# board.net
KiCad netlist of a schematic drawn in EAGLE
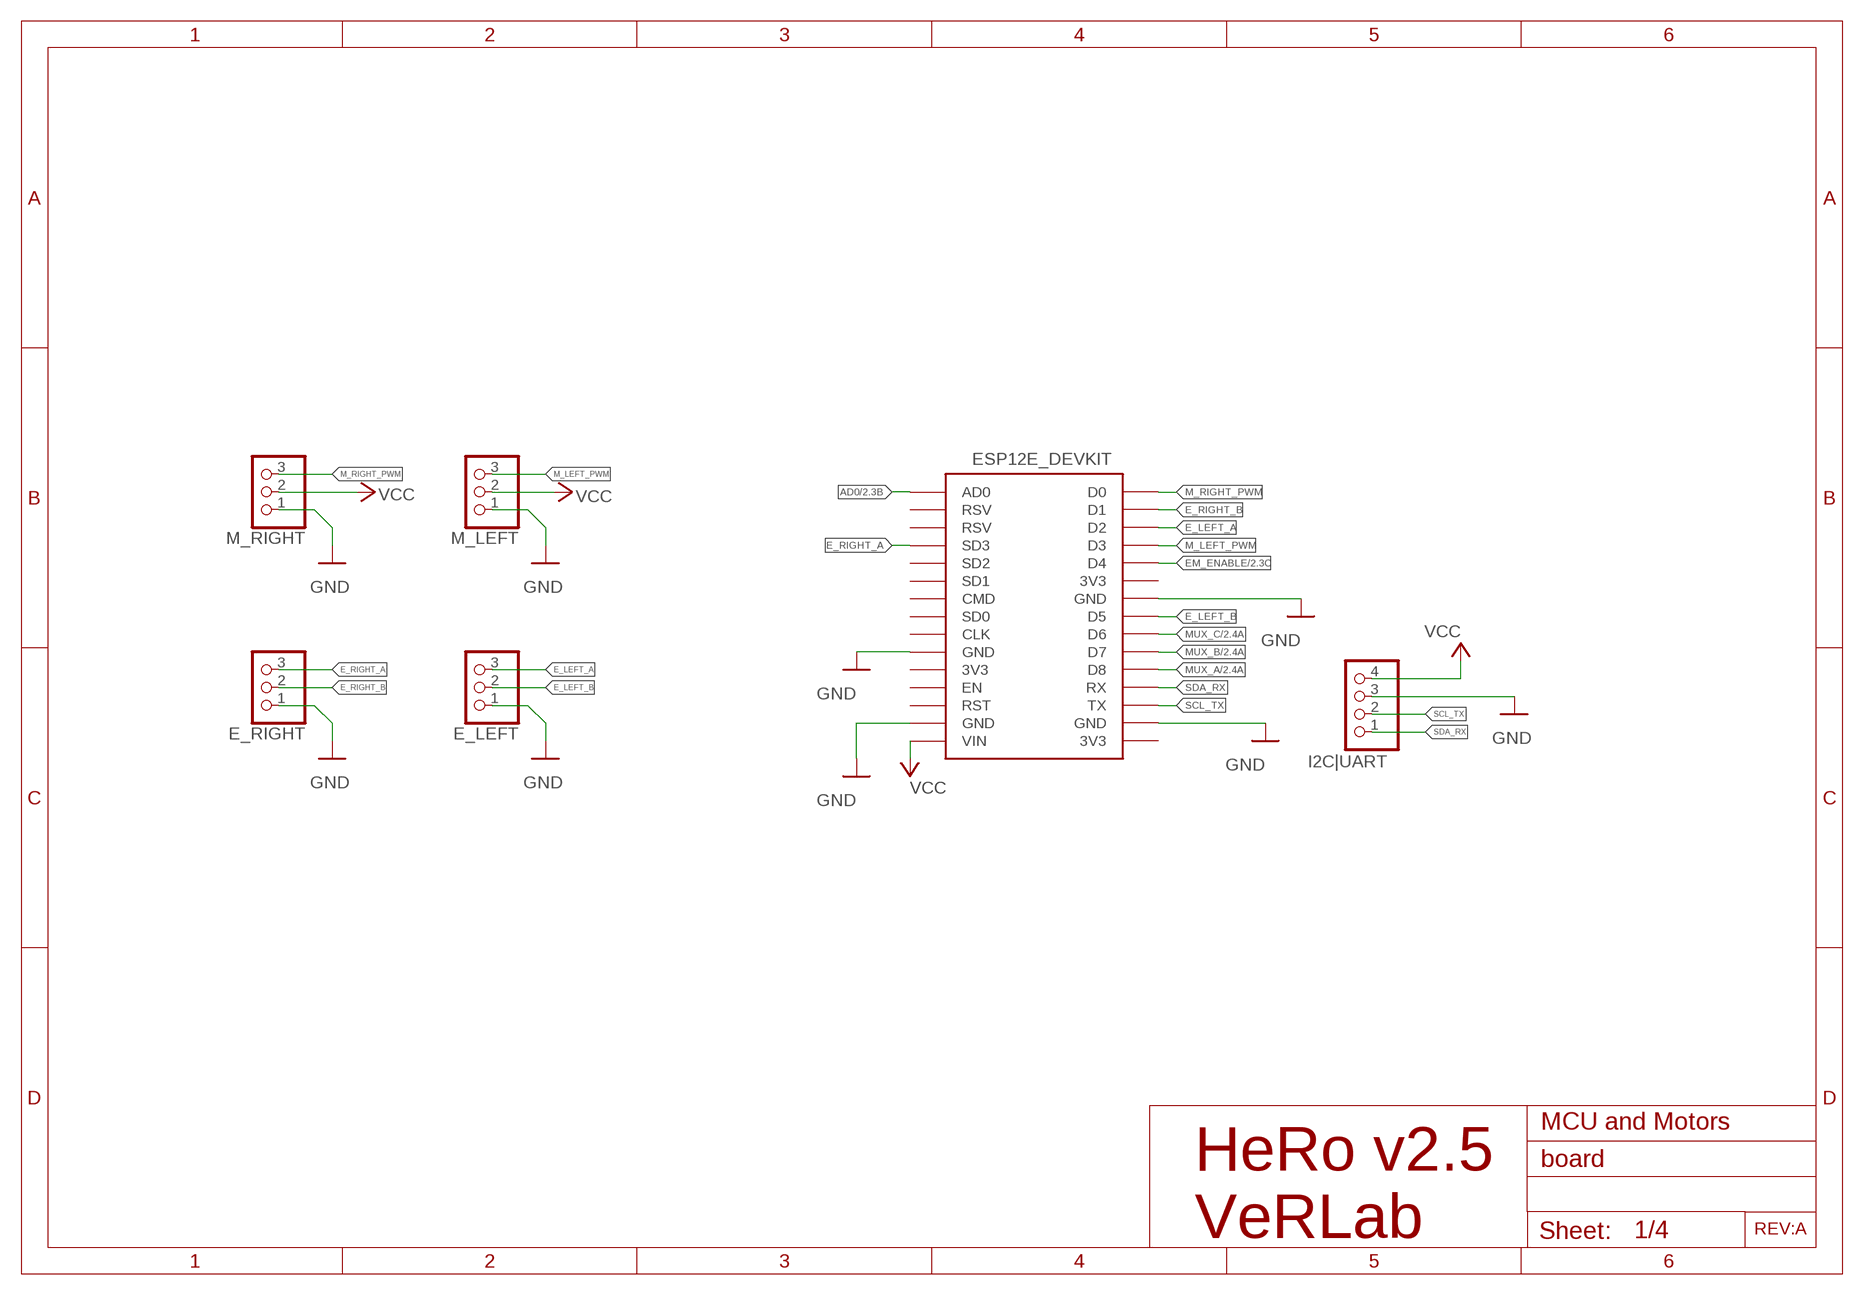
[diagram p0: schematic, sheet 1]
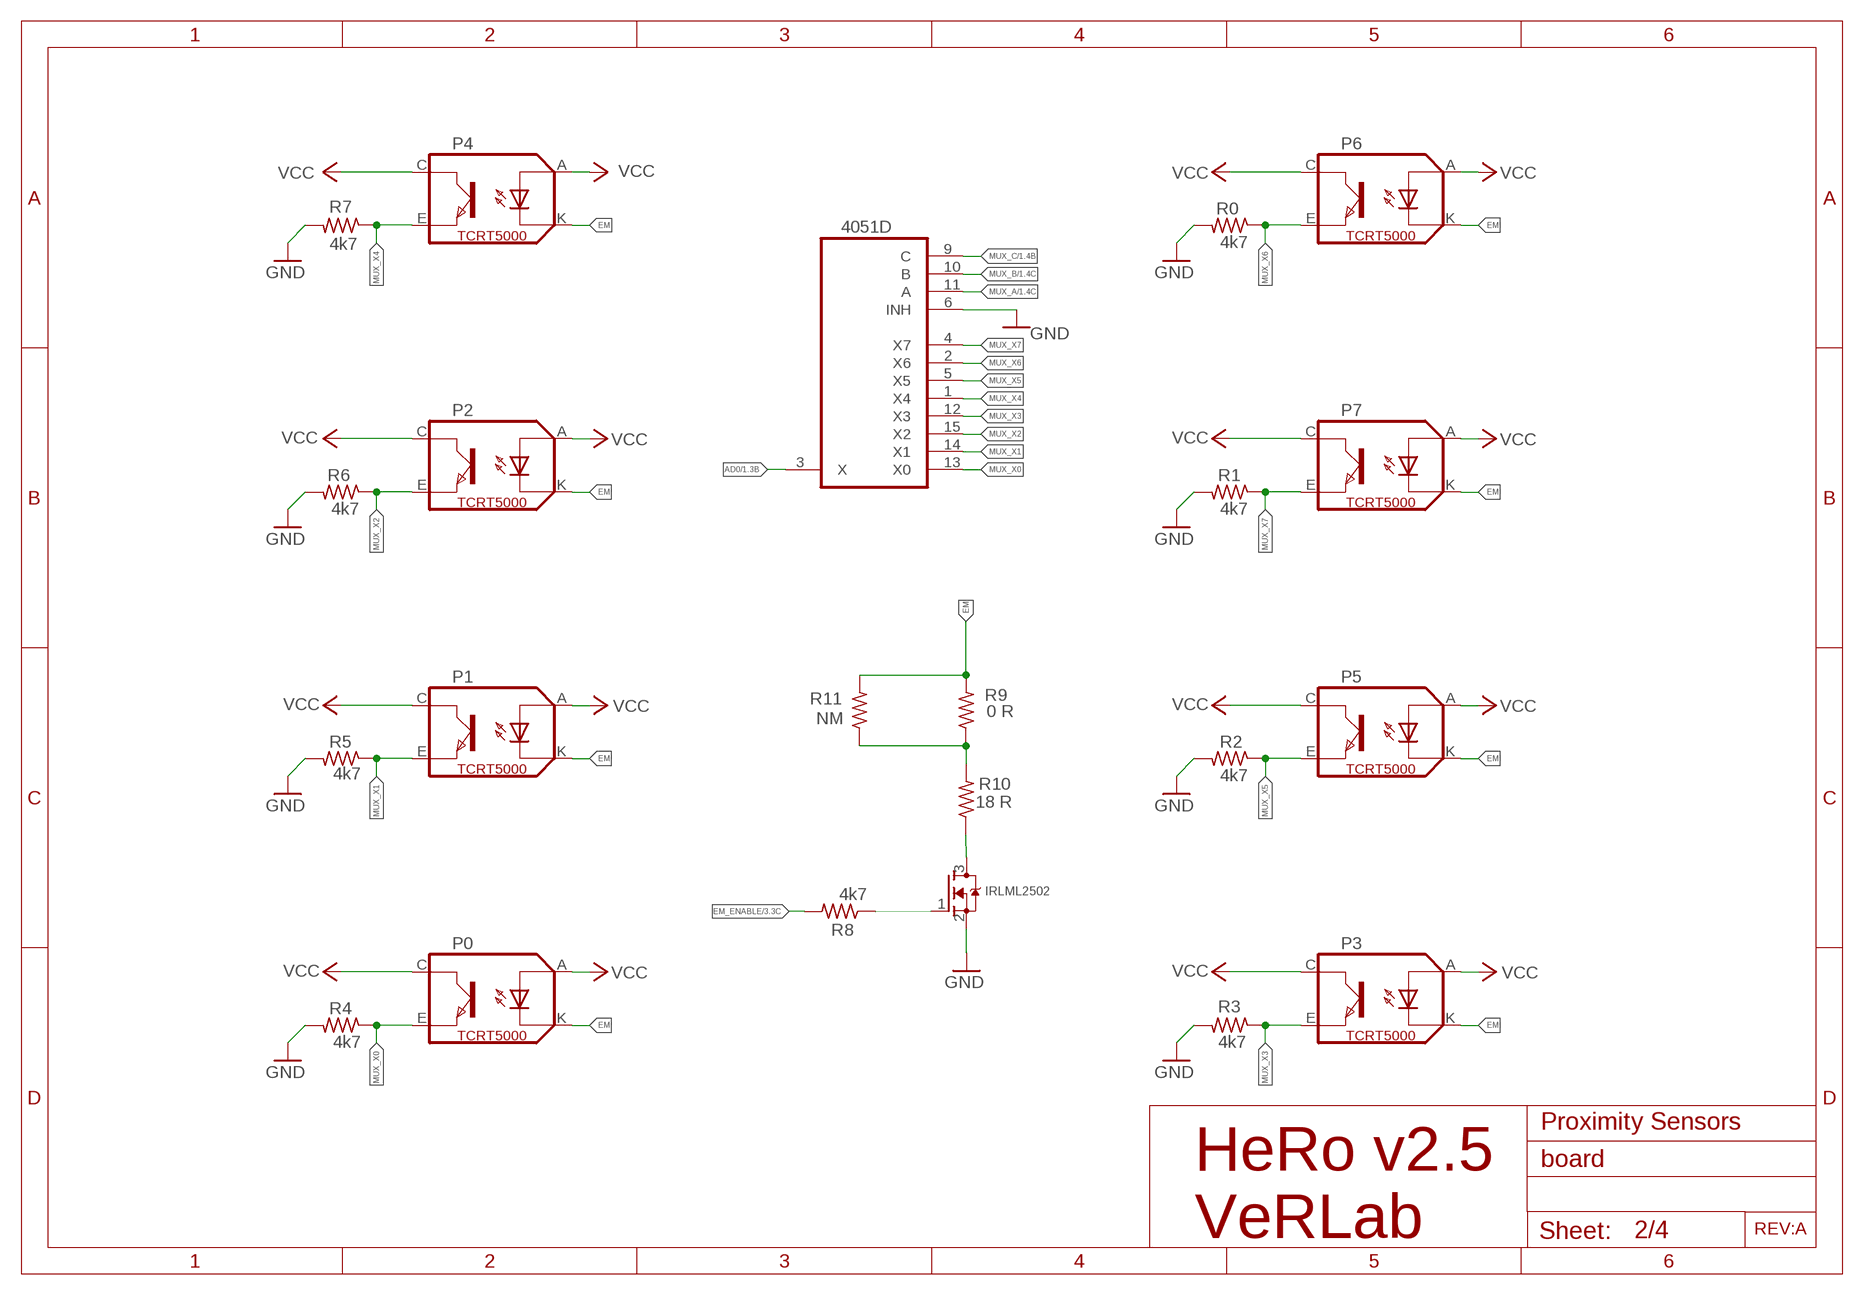
[diagram p1: schematic, sheet 2]
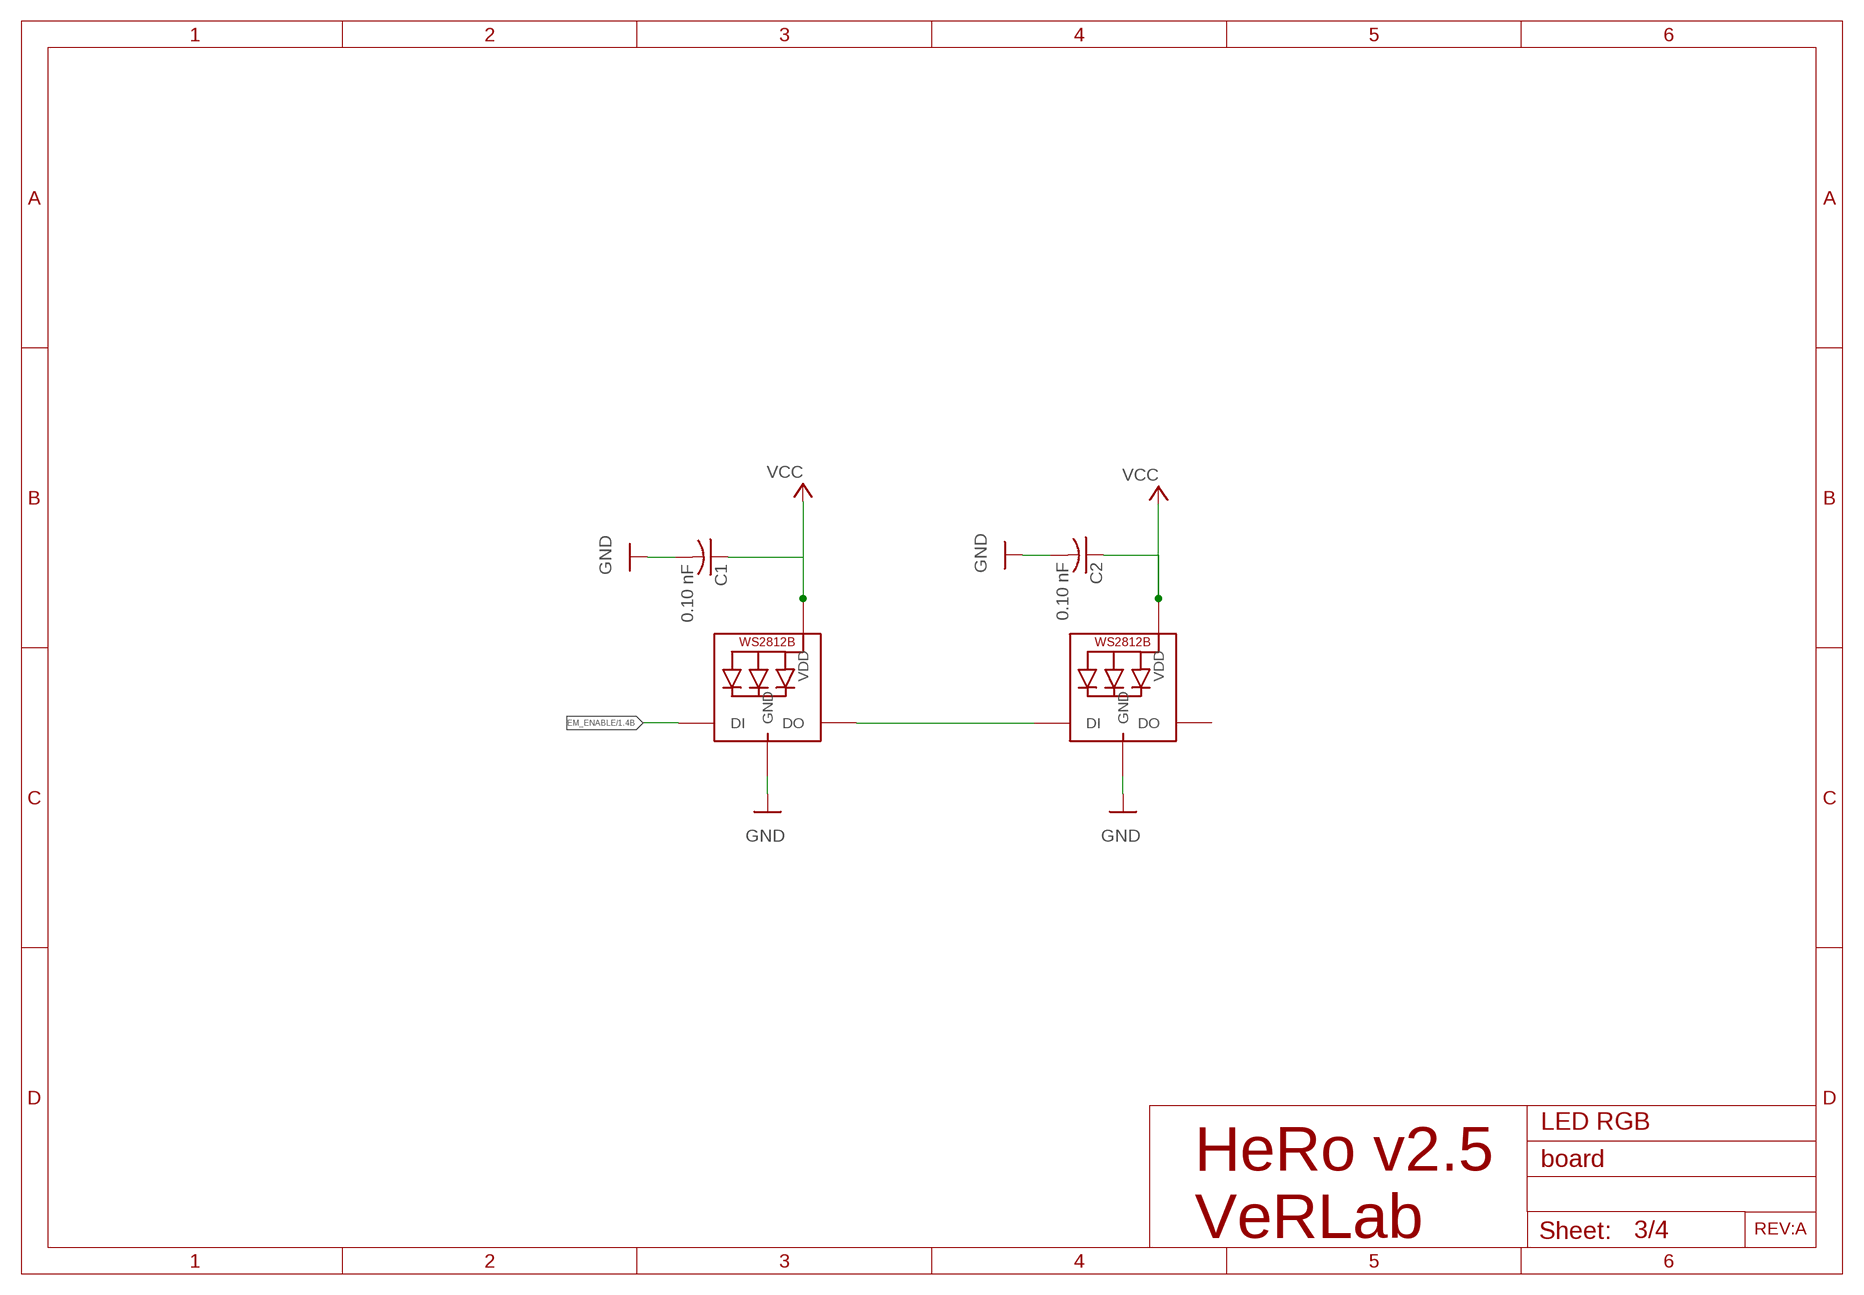
[diagram p2: schematic, sheet 3]
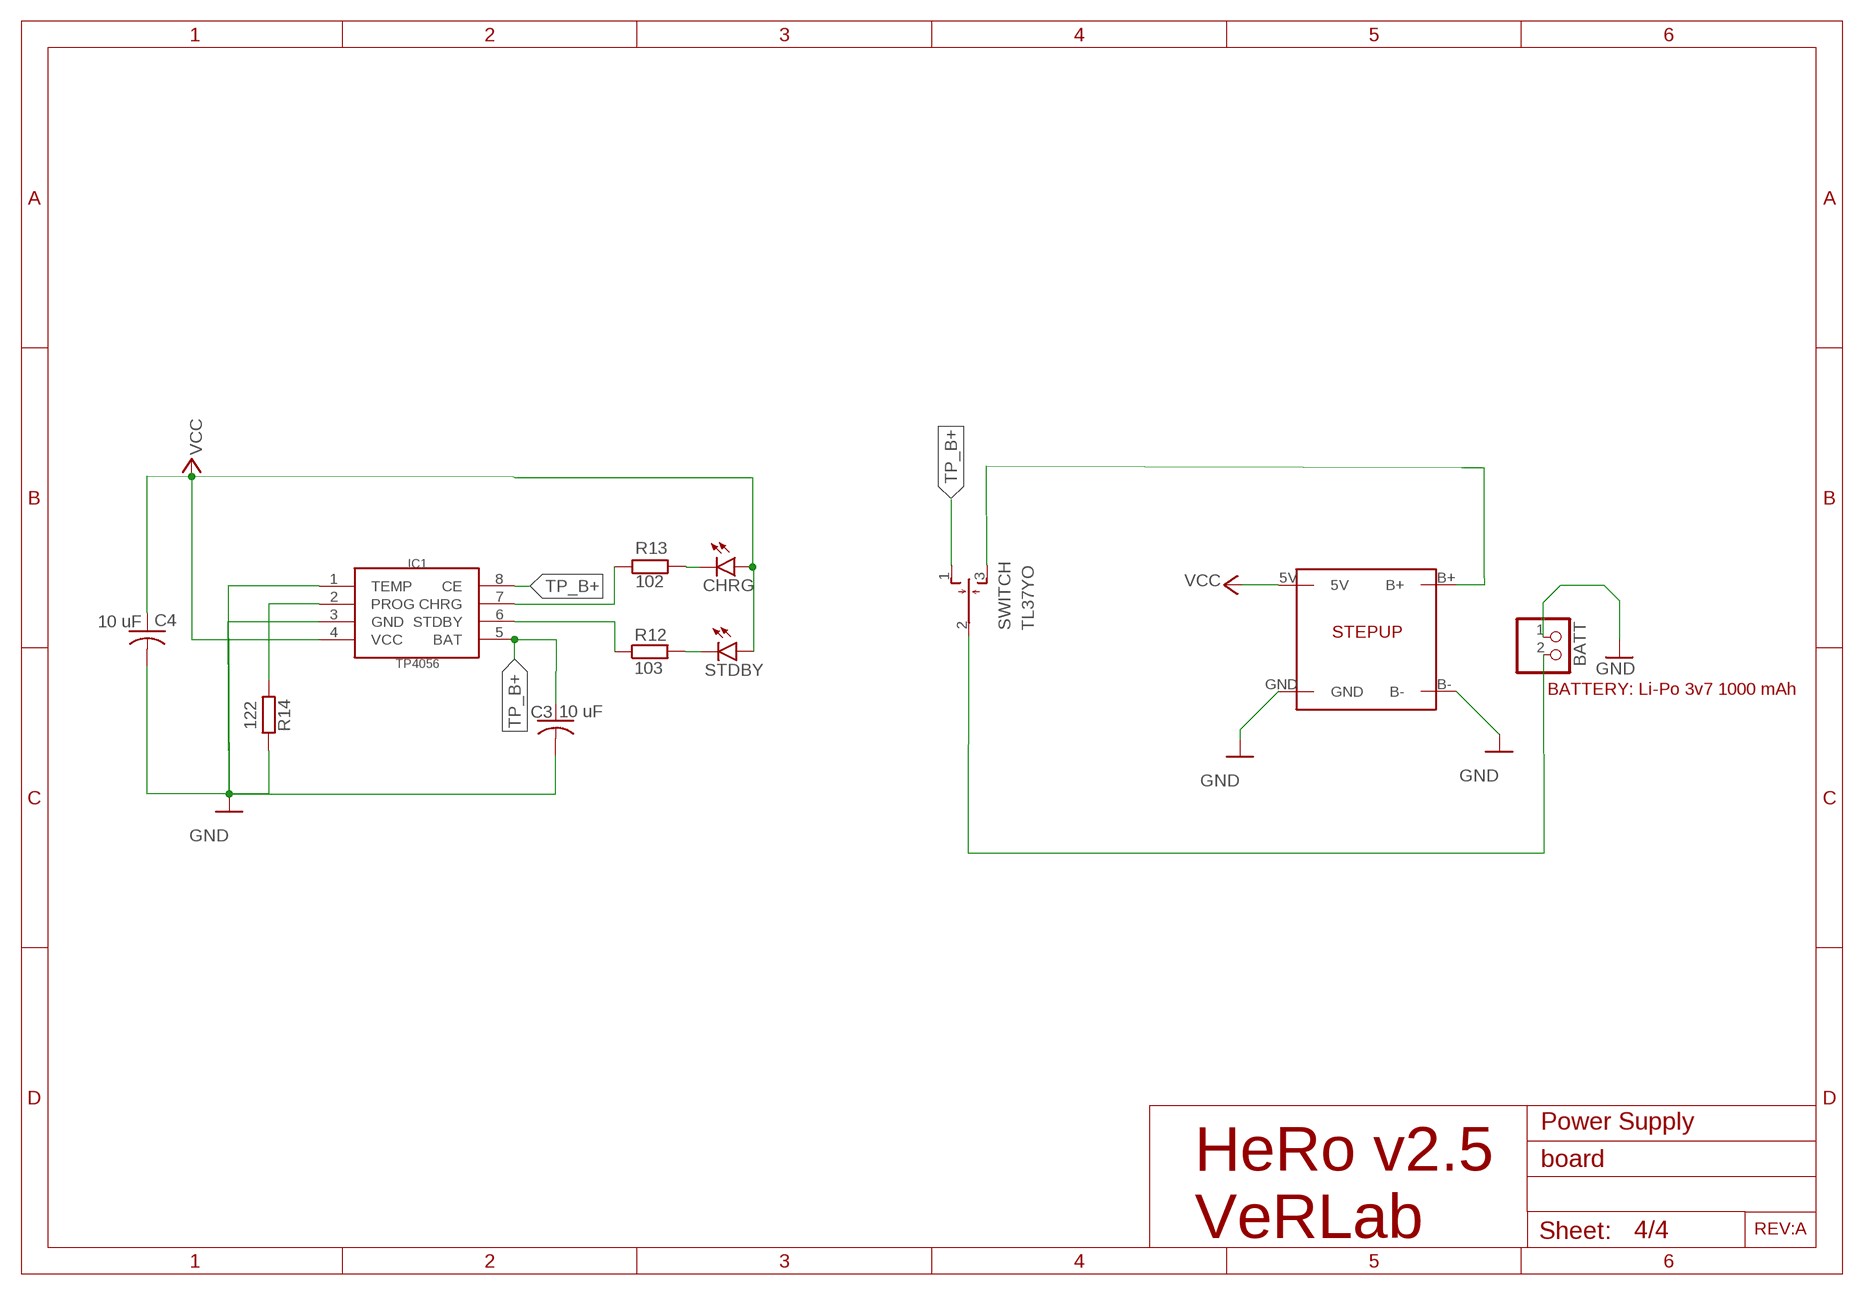
[diagram p3: schematic, sheet 4]

(export (version "E")
  (design (tool "Eeschema 10.0.6"))
  (components
    (comp (ref "BATT")
      (value "PINHD-1X2")
      (footprint "eagle-import:1X02")
      (libsource (lib "eagle-import") (part "PINHD-1X2"))
    )
    (comp (ref "C3")
      (value "10 uF")
      (footprint "eagle-import:C0603")
      (libsource (lib "eagle-import") (part "resistor_348_C-USC0603"))
    )
    (comp (ref "C4")
      (value "10 uF")
      (footprint "eagle-import:C0603")
      (libsource (lib "eagle-import") (part "resistor_348_C-USC0603"))
    )
    (comp (ref "CHRG")
      (value "LEDSML0805")
      (footprint "eagle-import:SML0805")
      (libsource (lib "eagle-import") (part "LEDSML0805"))
    )
    (comp (ref "IC1")
      (value "TP4056")
      (footprint "eagle-import:SOP-8")
      (fields (field (name "SPICEPREFIX") "X"))
      (libsource (lib "eagle-import") (part "TP4056"))
    )
    (comp (ref "OS1")
      (value "STEPUP")
      (footprint "eagle-import:STEPUP")
      (libsource (lib "eagle-import") (part "STEPUP"))
    )
    (comp (ref "R12")
      (value "103")
      (footprint "eagle-import:R0805")
      (libsource (lib "eagle-import") (part "R-EU_R0805"))
    )
    (comp (ref "R13")
      (value "102")
      (footprint "eagle-import:R0805")
      (libsource (lib "eagle-import") (part "R-EU_R0805"))
    )
    (comp (ref "R14")
      (value "122")
      (footprint "eagle-import:R0603")
      (libsource (lib "eagle-import") (part "R-EU_R0603"))
    )
    (comp (ref "STDBY")
      (value "LEDSML0805")
      (footprint "eagle-import:SML0805")
      (libsource (lib "eagle-import") (part "LEDSML0805"))
    )
    (comp (ref "SWITCH")
      (value "TL37YO")
      (footprint "eagle-import:TL3XYO")
      (libsource (lib "eagle-import") (part "TL37YO"))
    )
    (comp (ref "E_LEFT")
      (value "PINHD-1X3")
      (footprint "eagle-import:1X03")
      (libsource (lib "eagle-import") (part "PINHD-1X3"))
    )
    (comp (ref "E_RIGHT")
      (value "PINHD-1X3")
      (footprint "eagle-import:1X03")
      (libsource (lib "eagle-import") (part "PINHD-1X3"))
    )
    (comp (ref "I2C|UART")
      (value "PINHD-1X4")
      (footprint "eagle-import:1X04")
      (libsource (lib "eagle-import") (part "PINHD-1X4"))
    )
    (comp (ref "M_LEFT")
      (value "PINHD-1X3")
      (footprint "eagle-import:1X03")
      (libsource (lib "eagle-import") (part "PINHD-1X3"))
    )
    (comp (ref "M_RIGHT")
      (value "PINHD-1X3")
      (footprint "eagle-import:1X03")
      (libsource (lib "eagle-import") (part "PINHD-1X3"))
    )
    (comp (ref "U$1")
      (value "ESP12E_DEVKIT")
      (footprint "eagle-import:ESP12E_DEVKIT")
      (libsource (lib "eagle-import") (part "ESP12E_DEVKIT"))
    )
    (comp (ref "IC2")
      (value "4051D")
      (footprint "eagle-import:SO16")
      (libsource (lib "eagle-import") (part "4051D"))
    )
    (comp (ref "IRLML2502")
      (value "MOSFET-NREFLOW")
      (footprint "eagle-import:SOT23")
      (libsource (lib "eagle-import") (part "MOSFET-NREFLOW"))
    )
    (comp (ref "P0")
      (value "TCRT5000")
      (footprint "eagle-import:TCRT5000")
      (libsource (lib "eagle-import") (part "TCRT5000"))
    )
    (comp (ref "P1")
      (value "TCRT5000")
      (footprint "eagle-import:TCRT5000")
      (libsource (lib "eagle-import") (part "TCRT5000"))
    )
    (comp (ref "P2")
      (value "TCRT5000")
      (footprint "eagle-import:TCRT5000")
      (libsource (lib "eagle-import") (part "TCRT5000"))
    )
    (comp (ref "P3")
      (value "TCRT5000")
      (footprint "eagle-import:TCRT5000")
      (libsource (lib "eagle-import") (part "TCRT5000"))
    )
    (comp (ref "P4")
      (value "TCRT5000")
      (footprint "eagle-import:TCRT5000")
      (libsource (lib "eagle-import") (part "TCRT5000"))
    )
    (comp (ref "P5")
      (value "TCRT5000")
      (footprint "eagle-import:TCRT5000")
      (libsource (lib "eagle-import") (part "TCRT5000"))
    )
    (comp (ref "P6")
      (value "TCRT5000")
      (footprint "eagle-import:TCRT5000")
      (libsource (lib "eagle-import") (part "TCRT5000"))
    )
    (comp (ref "P7")
      (value "TCRT5000")
      (footprint "eagle-import:TCRT5000")
      (libsource (lib "eagle-import") (part "TCRT5000"))
    )
    (comp (ref "R0")
      (value "4k7")
      (footprint "eagle-import:M0805")
      (libsource (lib "eagle-import") (part "R-US_M0805"))
    )
    (comp (ref "R1")
      (value "4k7")
      (footprint "eagle-import:M0805")
      (libsource (lib "eagle-import") (part "R-US_M0805"))
    )
    (comp (ref "R2")
      (value "4k7")
      (footprint "eagle-import:M0805")
      (libsource (lib "eagle-import") (part "R-US_M0805"))
    )
    (comp (ref "R3")
      (value "4k7")
      (footprint "eagle-import:M0805")
      (libsource (lib "eagle-import") (part "R-US_M0805"))
    )
    (comp (ref "R4")
      (value "4k7")
      (footprint "eagle-import:M0805")
      (libsource (lib "eagle-import") (part "R-US_M0805"))
    )
    (comp (ref "R5")
      (value "4k7")
      (footprint "eagle-import:M0805")
      (libsource (lib "eagle-import") (part "R-US_M0805"))
    )
    (comp (ref "R6")
      (value "4k7")
      (footprint "eagle-import:M0805")
      (libsource (lib "eagle-import") (part "R-US_M0805"))
    )
    (comp (ref "R7")
      (value "4k7")
      (footprint "eagle-import:M0805")
      (libsource (lib "eagle-import") (part "R-US_M0805"))
    )
    (comp (ref "R8")
      (value "4k7")
      (footprint "eagle-import:R0805")
      (fields (field (name "SPICEPREFIX") "R"))
      (libsource (lib "eagle-import") (part "resistor_348_R-US_R0805"))
    )
    (comp (ref "R9")
      (value "0 R")
      (footprint "eagle-import:R0805")
      (fields (field (name "SPICEPREFIX") "R"))
      (libsource (lib "eagle-import") (part "resistor_348_R-US_R0805"))
    )
    (comp (ref "R10")
      (value "18 R")
      (footprint "eagle-import:R0805")
      (fields (field (name "SPICEPREFIX") "R"))
      (libsource (lib "eagle-import") (part "resistor_348_R-US_R0805"))
    )
    (comp (ref "R11")
      (value "NM")
      (footprint "eagle-import:R0805")
      (fields (field (name "SPICEPREFIX") "R"))
      (libsource (lib "eagle-import") (part "resistor_348_R-US_R0805"))
    )
    (comp (ref "C1")
      (value "0.10 nF")
      (footprint "eagle-import:C0603")
      (libsource (lib "eagle-import") (part "C-USC0603"))
    )
    (comp (ref "C2")
      (value "0.10 nF")
      (footprint "eagle-import:C0603")
      (libsource (lib "eagle-import") (part "C-USC0603"))
    )
    (comp (ref "LED0")
      (value "WS2812B5050")
      (footprint "eagle-import:WS2812B")
      (libsource (lib "eagle-import") (part "WS2812B5050"))
    )
    (comp (ref "LED1")
      (value "WS2812B5050")
      (footprint "eagle-import:WS2812B")
      (libsource (lib "eagle-import") (part "WS2812B5050"))
    )
  )
  (nets
    (net (code "1") (name "AD0") (class "Default")
      (node (ref "IC2") (pin "3") (pinfunction "X_3") (pintype "bidirectional"))
      (node (ref "U$1") (pin "AD0") (pinfunction "AD0_AD0") (pintype "bidirectional"))
    )
    (net (code "2") (name "EM") (class "Default")
      (node (ref "P0") (pin "K") (pinfunction "CATHODE_K") (pintype "passive"))
      (node (ref "P1") (pin "K") (pinfunction "CATHODE_K") (pintype "passive"))
      (node (ref "P2") (pin "K") (pinfunction "CATHODE_K") (pintype "passive"))
      (node (ref "P3") (pin "K") (pinfunction "CATHODE_K") (pintype "passive"))
      (node (ref "P4") (pin "K") (pinfunction "CATHODE_K") (pintype "passive"))
      (node (ref "P5") (pin "K") (pinfunction "CATHODE_K") (pintype "passive"))
      (node (ref "P6") (pin "K") (pinfunction "CATHODE_K") (pintype "passive"))
      (node (ref "P7") (pin "K") (pinfunction "CATHODE_K") (pintype "passive"))
      (node (ref "R11") (pin "2") (pinfunction "2_2") (pintype "passive"))
      (node (ref "R9") (pin "2") (pinfunction "2_2") (pintype "passive"))
    )
    (net (code "3") (name "EM_ENABLE") (class "Default")
      (node (ref "LED0") (pin "4-DIN") (pinfunction "DI_4-DIN") (pintype "input"))
      (node (ref "R8") (pin "2") (pinfunction "2_2") (pintype "passive"))
      (node (ref "U$1") (pin "D4") (pinfunction "D4_D4") (pintype "bidirectional"))
    )
    (net (code "4") (name "E_LEFT_A") (class "Default")
      (node (ref "E_LEFT") (pin "3") (pinfunction "3_3") (pintype "passive"))
      (node (ref "U$1") (pin "D2") (pinfunction "D2_D2") (pintype "bidirectional"))
    )
    (net (code "5") (name "E_LEFT_B") (class "Default")
      (node (ref "E_LEFT") (pin "2") (pinfunction "2_2") (pintype "passive"))
      (node (ref "U$1") (pin "D5") (pinfunction "D5_D5") (pintype "bidirectional"))
    )
    (net (code "6") (name "E_RIGHT_A") (class "Default")
      (node (ref "E_RIGHT") (pin "3") (pinfunction "3_3") (pintype "passive"))
      (node (ref "U$1") (pin "SD3") (pinfunction "SD3_SD3") (pintype "bidirectional"))
    )
    (net (code "7") (name "E_RIGHT_B") (class "Default")
      (node (ref "E_RIGHT") (pin "2") (pinfunction "2_2") (pintype "passive"))
      (node (ref "U$1") (pin "D1") (pinfunction "D1_D1") (pintype "bidirectional"))
    )
    (net (code "8") (name "GND") (class "Default")
      (node (ref "BATT") (pin "1") (pinfunction "1_1") (pintype "passive"))
      (node (ref "C1") (pin "2") (pinfunction "2_2") (pintype "passive"))
      (node (ref "C2") (pin "2") (pinfunction "2_2") (pintype "passive"))
      (node (ref "C3") (pin "2") (pinfunction "2_2") (pintype "passive"))
      (node (ref "C4") (pin "2") (pinfunction "2_2") (pintype "passive"))
      (node (ref "E_LEFT") (pin "1") (pinfunction "1_1") (pintype "passive"))
      (node (ref "E_RIGHT") (pin "1") (pinfunction "1_1") (pintype "passive"))
      (node (ref "I2C|UART") (pin "3") (pinfunction "3_3") (pintype "passive"))
      (node (ref "IC1") (pin "1") (pinfunction "TEMP_1") (pintype "bidirectional"))
      (node (ref "IC1") (pin "3") (pinfunction "GND_3") (pintype "bidirectional"))
      (node (ref "IC2") (pin "6") (pinfunction "INH_6") (pintype "input"))
      (node (ref "IRLML2502") (pin "2") (pinfunction "S_2") (pintype "bidirectional"))
      (node (ref "LED0") (pin "3-GND") (pinfunction "GND_3-GND") (pintype "power_in"))
      (node (ref "LED1") (pin "3-GND") (pinfunction "GND_3-GND") (pintype "power_in"))
      (node (ref "M_LEFT") (pin "1") (pinfunction "1_1") (pintype "passive"))
      (node (ref "M_RIGHT") (pin "1") (pinfunction "1_1") (pintype "passive"))
      (node (ref "OS1") (pin "B-") (pinfunction "B-_B-") (pintype "input"))
      (node (ref "OS1") (pin "GND") (pinfunction "GND_GND") (pintype "output"))
      (node (ref "R0") (pin "2") (pinfunction "2_2") (pintype "passive"))
      (node (ref "R1") (pin "2") (pinfunction "2_2") (pintype "passive"))
      (node (ref "R14") (pin "1") (pinfunction "1_1") (pintype "passive"))
      (node (ref "R2") (pin "2") (pinfunction "2_2") (pintype "passive"))
      (node (ref "R3") (pin "2") (pinfunction "2_2") (pintype "passive"))
      (node (ref "R4") (pin "2") (pinfunction "2_2") (pintype "passive"))
      (node (ref "R5") (pin "2") (pinfunction "2_2") (pintype "passive"))
      (node (ref "R6") (pin "2") (pinfunction "2_2") (pintype "passive"))
      (node (ref "R7") (pin "2") (pinfunction "2_2") (pintype "passive"))
      (node (ref "U$1") (pin "GND@0") (pinfunction "GND_GND@0") (pintype "bidirectional"))
      (node (ref "U$1") (pin "GND@1") (pinfunction "GND_GND@1") (pintype "bidirectional"))
      (node (ref "U$1") (pin "GND@2") (pinfunction "GND_GND@2") (pintype "bidirectional"))
      (node (ref "U$1") (pin "GND@3") (pinfunction "GND_GND@3") (pintype "bidirectional"))
    )
    (net (code "9") (name "MUX_A") (class "Default")
      (node (ref "IC2") (pin "11") (pinfunction "A_11") (pintype "input"))
      (node (ref "U$1") (pin "D8") (pinfunction "D8_D8") (pintype "bidirectional"))
    )
    (net (code "10") (name "MUX_B") (class "Default")
      (node (ref "IC2") (pin "10") (pinfunction "B_10") (pintype "input"))
      (node (ref "U$1") (pin "D7") (pinfunction "D7_D7") (pintype "bidirectional"))
    )
    (net (code "11") (name "MUX_C") (class "Default")
      (node (ref "IC2") (pin "9") (pinfunction "C_9") (pintype "input"))
      (node (ref "U$1") (pin "D6") (pinfunction "D6_D6") (pintype "bidirectional"))
    )
    (net (code "12") (name "MUX_X0") (class "Default")
      (node (ref "IC2") (pin "13") (pinfunction "X0_13") (pintype "bidirectional"))
      (node (ref "P0") (pin "E") (pinfunction "EMITTER_E") (pintype "passive"))
      (node (ref "R4") (pin "1") (pinfunction "1_1") (pintype "passive"))
    )
    (net (code "13") (name "MUX_X1") (class "Default")
      (node (ref "IC2") (pin "14") (pinfunction "X1_14") (pintype "bidirectional"))
      (node (ref "P1") (pin "E") (pinfunction "EMITTER_E") (pintype "passive"))
      (node (ref "R5") (pin "1") (pinfunction "1_1") (pintype "passive"))
    )
    (net (code "14") (name "MUX_X2") (class "Default")
      (node (ref "IC2") (pin "15") (pinfunction "X2_15") (pintype "bidirectional"))
      (node (ref "P2") (pin "E") (pinfunction "EMITTER_E") (pintype "passive"))
      (node (ref "R6") (pin "1") (pinfunction "1_1") (pintype "passive"))
    )
    (net (code "15") (name "MUX_X3") (class "Default")
      (node (ref "IC2") (pin "12") (pinfunction "X3_12") (pintype "bidirectional"))
      (node (ref "P3") (pin "E") (pinfunction "EMITTER_E") (pintype "passive"))
      (node (ref "R3") (pin "1") (pinfunction "1_1") (pintype "passive"))
    )
    (net (code "16") (name "MUX_X4") (class "Default")
      (node (ref "IC2") (pin "1") (pinfunction "X4_1") (pintype "bidirectional"))
      (node (ref "P4") (pin "E") (pinfunction "EMITTER_E") (pintype "passive"))
      (node (ref "R7") (pin "1") (pinfunction "1_1") (pintype "passive"))
    )
    (net (code "17") (name "MUX_X5") (class "Default")
      (node (ref "IC2") (pin "5") (pinfunction "X5_5") (pintype "bidirectional"))
      (node (ref "P5") (pin "E") (pinfunction "EMITTER_E") (pintype "passive"))
      (node (ref "R2") (pin "1") (pinfunction "1_1") (pintype "passive"))
    )
    (net (code "18") (name "MUX_X6") (class "Default")
      (node (ref "IC2") (pin "2") (pinfunction "X6_2") (pintype "bidirectional"))
      (node (ref "P6") (pin "E") (pinfunction "EMITTER_E") (pintype "passive"))
      (node (ref "R0") (pin "1") (pinfunction "1_1") (pintype "passive"))
    )
    (net (code "19") (name "MUX_X7") (class "Default")
      (node (ref "IC2") (pin "4") (pinfunction "X7_4") (pintype "bidirectional"))
      (node (ref "P7") (pin "E") (pinfunction "EMITTER_E") (pintype "passive"))
      (node (ref "R1") (pin "1") (pinfunction "1_1") (pintype "passive"))
    )
    (net (code "20") (name "M_LEFT_PWM") (class "Default")
      (node (ref "M_LEFT") (pin "3") (pinfunction "3_3") (pintype "passive"))
      (node (ref "U$1") (pin "D3") (pinfunction "D3_D3") (pintype "bidirectional"))
    )
    (net (code "21") (name "M_RIGHT_PWM") (class "Default")
      (node (ref "M_RIGHT") (pin "3") (pinfunction "3_3") (pintype "passive"))
      (node (ref "U$1") (pin "D0") (pinfunction "D0_D0") (pintype "bidirectional"))
    )
    (net (code "22") (name "Net-(CHRG-PadA)") (class "Default")
      (node (ref "CHRG") (pin "A") (pinfunction "A_A") (pintype "passive"))
      (node (ref "STDBY") (pin "A") (pinfunction "A_A") (pintype "passive"))
    )
    (net (code "23") (name "Net-(CHRG-PadC)") (class "Default")
      (node (ref "CHRG") (pin "C") (pinfunction "C_C") (pintype "passive"))
      (node (ref "R13") (pin "2") (pinfunction "2_2") (pintype "passive"))
    )
    (net (code "24") (name "Net-(IC1-CHRG)") (class "Default")
      (node (ref "IC1") (pin "7") (pinfunction "CHRG_7") (pintype "bidirectional"))
      (node (ref "R13") (pin "1") (pinfunction "1_1") (pintype "passive"))
    )
    (net (code "25") (name "Net-(IC1-PROG)") (class "Default")
      (node (ref "IC1") (pin "2") (pinfunction "PROG_2") (pintype "bidirectional"))
      (node (ref "R14") (pin "2") (pinfunction "2_2") (pintype "passive"))
    )
    (net (code "26") (name "Net-(IC1-STDBY)") (class "Default")
      (node (ref "IC1") (pin "6") (pinfunction "STDBY_6") (pintype "bidirectional"))
      (node (ref "R12") (pin "1") (pinfunction "1_1") (pintype "passive"))
    )
    (net (code "27") (name "Net-(IRLML2502-D)") (class "Default")
      (node (ref "IRLML2502") (pin "3") (pinfunction "D_3") (pintype "bidirectional"))
      (node (ref "R10") (pin "1") (pinfunction "1_1") (pintype "passive"))
    )
    (net (code "28") (name "Net-(IRLML2502-G)") (class "Default")
      (node (ref "IRLML2502") (pin "1") (pinfunction "G_1") (pintype "bidirectional"))
      (node (ref "R8") (pin "1") (pinfunction "1_1") (pintype "passive"))
    )
    (net (code "29") (name "Net-(LED0-DO)") (class "Default")
      (node (ref "LED0") (pin "2-DOUT") (pinfunction "DO_2-DOUT") (pintype "output"))
      (node (ref "LED1") (pin "4-DIN") (pinfunction "DI_4-DIN") (pintype "input"))
    )
    (net (code "30") (name "Net-(R10-Pad2)") (class "Default")
      (node (ref "R10") (pin "2") (pinfunction "2_2") (pintype "passive"))
      (node (ref "R11") (pin "1") (pinfunction "1_1") (pintype "passive"))
      (node (ref "R9") (pin "1") (pinfunction "1_1") (pintype "passive"))
    )
    (net (code "31") (name "Net-(R12-Pad2)") (class "Default")
      (node (ref "R12") (pin "2") (pinfunction "2_2") (pintype "passive"))
      (node (ref "STDBY") (pin "C") (pinfunction "C_C") (pintype "passive"))
    )
    (net (code "32") (name "Net-(SWITCH-P)") (class "Default")
      (node (ref "BATT") (pin "2") (pinfunction "2_2") (pintype "passive"))
      (node (ref "SWITCH") (pin "2") (pinfunction "P_2") (pintype "passive"))
    )
    (net (code "33") (name "Net-(SWITCH-S)") (class "Default")
      (node (ref "OS1") (pin "B+") (pinfunction "B+_B+") (pintype "input"))
      (node (ref "SWITCH") (pin "3") (pinfunction "S_3") (pintype "passive"))
    )
    (net (code "34") (name "SCL_TX") (class "Default")
      (node (ref "I2C|UART") (pin "2") (pinfunction "2_2") (pintype "passive"))
      (node (ref "U$1") (pin "TX") (pinfunction "TX_TX") (pintype "bidirectional"))
    )
    (net (code "35") (name "SDA_RX") (class "Default")
      (node (ref "I2C|UART") (pin "1") (pinfunction "1_1") (pintype "passive"))
      (node (ref "U$1") (pin "RX") (pinfunction "RX_RX") (pintype "bidirectional"))
    )
    (net (code "36") (name "TP_B+") (class "Default")
      (node (ref "C3") (pin "1") (pinfunction "1_1") (pintype "passive"))
      (node (ref "IC1") (pin "5") (pinfunction "BAT_5") (pintype "bidirectional"))
      (node (ref "IC1") (pin "8") (pinfunction "CE_8") (pintype "bidirectional"))
      (node (ref "SWITCH") (pin "1") (pinfunction "O_1") (pintype "passive"))
    )
    (net (code "37") (name "VCC") (class "Default")
      (node (ref "C1") (pin "1") (pinfunction "1_1") (pintype "passive"))
      (node (ref "C2") (pin "1") (pinfunction "1_1") (pintype "passive"))
      (node (ref "C4") (pin "1") (pinfunction "1_1") (pintype "passive"))
      (node (ref "I2C|UART") (pin "4") (pinfunction "4_4") (pintype "passive"))
      (node (ref "IC1") (pin "4") (pinfunction "VCC_4") (pintype "bidirectional"))
      (node (ref "LED0") (pin "1-VDD") (pinfunction "VDD_1-VDD") (pintype "power_in"))
      (node (ref "LED1") (pin "1-VDD") (pinfunction "VDD_1-VDD") (pintype "power_in"))
      (node (ref "M_LEFT") (pin "2") (pinfunction "2_2") (pintype "passive"))
      (node (ref "M_RIGHT") (pin "2") (pinfunction "2_2") (pintype "passive"))
      (node (ref "OS1") (pin "5V") (pinfunction "5V_5V") (pintype "output"))
      (node (ref "P0") (pin "A") (pinfunction "ANODE_A") (pintype "passive"))
      (node (ref "P0") (pin "C") (pinfunction "COLLECTOR_C") (pintype "passive"))
      (node (ref "P1") (pin "A") (pinfunction "ANODE_A") (pintype "passive"))
      (node (ref "P1") (pin "C") (pinfunction "COLLECTOR_C") (pintype "passive"))
      (node (ref "P2") (pin "A") (pinfunction "ANODE_A") (pintype "passive"))
      (node (ref "P2") (pin "C") (pinfunction "COLLECTOR_C") (pintype "passive"))
      (node (ref "P3") (pin "A") (pinfunction "ANODE_A") (pintype "passive"))
      (node (ref "P3") (pin "C") (pinfunction "COLLECTOR_C") (pintype "passive"))
      (node (ref "P4") (pin "A") (pinfunction "ANODE_A") (pintype "passive"))
      (node (ref "P4") (pin "C") (pinfunction "COLLECTOR_C") (pintype "passive"))
      (node (ref "P5") (pin "A") (pinfunction "ANODE_A") (pintype "passive"))
      (node (ref "P5") (pin "C") (pinfunction "COLLECTOR_C") (pintype "passive"))
      (node (ref "P6") (pin "A") (pinfunction "ANODE_A") (pintype "passive"))
      (node (ref "P6") (pin "C") (pinfunction "COLLECTOR_C") (pintype "passive"))
      (node (ref "P7") (pin "A") (pinfunction "ANODE_A") (pintype "passive"))
      (node (ref "P7") (pin "C") (pinfunction "COLLECTOR_C") (pintype "passive"))
      (node (ref "U$1") (pin "VIN") (pinfunction "VIN_VIN") (pintype "bidirectional"))
    )
    (net (code "38") (name "unconnected-(LED1-DO-Pad2-DOUT)") (class "Default")
      (node (ref "LED1") (pin "2-DOUT") (pinfunction "DO_2-DOUT") (pintype "output"))
    )
    (net (code "39") (name "unconnected-(U$1-3V3-Pad3V3@0)") (class "Default")
      (node (ref "U$1") (pin "3V3@0") (pinfunction "3V3_3V3@0") (pintype "bidirectional"))
    )
    (net (code "40") (name "unconnected-(U$1-3V3-Pad3V3@1)") (class "Default")
      (node (ref "U$1") (pin "3V3@1") (pinfunction "3V3_3V3@1") (pintype "bidirectional"))
    )
    (net (code "41") (name "unconnected-(U$1-3V3-Pad3V3@2)") (class "Default")
      (node (ref "U$1") (pin "3V3@2") (pinfunction "3V3_3V3@2") (pintype "bidirectional"))
    )
    (net (code "42") (name "unconnected-(U$1-PadCLK)") (class "Default")
      (node (ref "U$1") (pin "CLK") (pinfunction "CLK_CLK") (pintype "bidirectional"))
    )
    (net (code "43") (name "unconnected-(U$1-PadCMD)") (class "Default")
      (node (ref "U$1") (pin "CMD") (pinfunction "CMD_CMD") (pintype "bidirectional"))
    )
    (net (code "44") (name "unconnected-(U$1-PadEN)") (class "Default")
      (node (ref "U$1") (pin "EN") (pinfunction "EN_EN") (pintype "bidirectional"))
    )
    (net (code "45") (name "unconnected-(U$1-PadRST)") (class "Default")
      (node (ref "U$1") (pin "RST") (pinfunction "RST_RST") (pintype "bidirectional"))
    )
    (net (code "46") (name "unconnected-(U$1-PadSD0)") (class "Default")
      (node (ref "U$1") (pin "SD0") (pinfunction "SD0_SD0") (pintype "bidirectional"))
    )
    (net (code "47") (name "unconnected-(U$1-PadSD1)") (class "Default")
      (node (ref "U$1") (pin "SD1") (pinfunction "SD1_SD1") (pintype "bidirectional"))
    )
    (net (code "48") (name "unconnected-(U$1-PadSD2)") (class "Default")
      (node (ref "U$1") (pin "SD2") (pinfunction "SD2_SD2") (pintype "bidirectional"))
    )
    (net (code "49") (name "unconnected-(U$1-RSV-PadRSV@0)") (class "Default")
      (node (ref "U$1") (pin "RSV@0") (pinfunction "RSV_RSV@0") (pintype "bidirectional"))
    )
    (net (code "50") (name "unconnected-(U$1-RSV-PadRSV@1)") (class "Default")
      (node (ref "U$1") (pin "RSV@1") (pinfunction "RSV_RSV@1") (pintype "bidirectional"))
    )
  )
)
